# board_0_8v.net
KiCad netlist of a schematic drawn in EAGLE
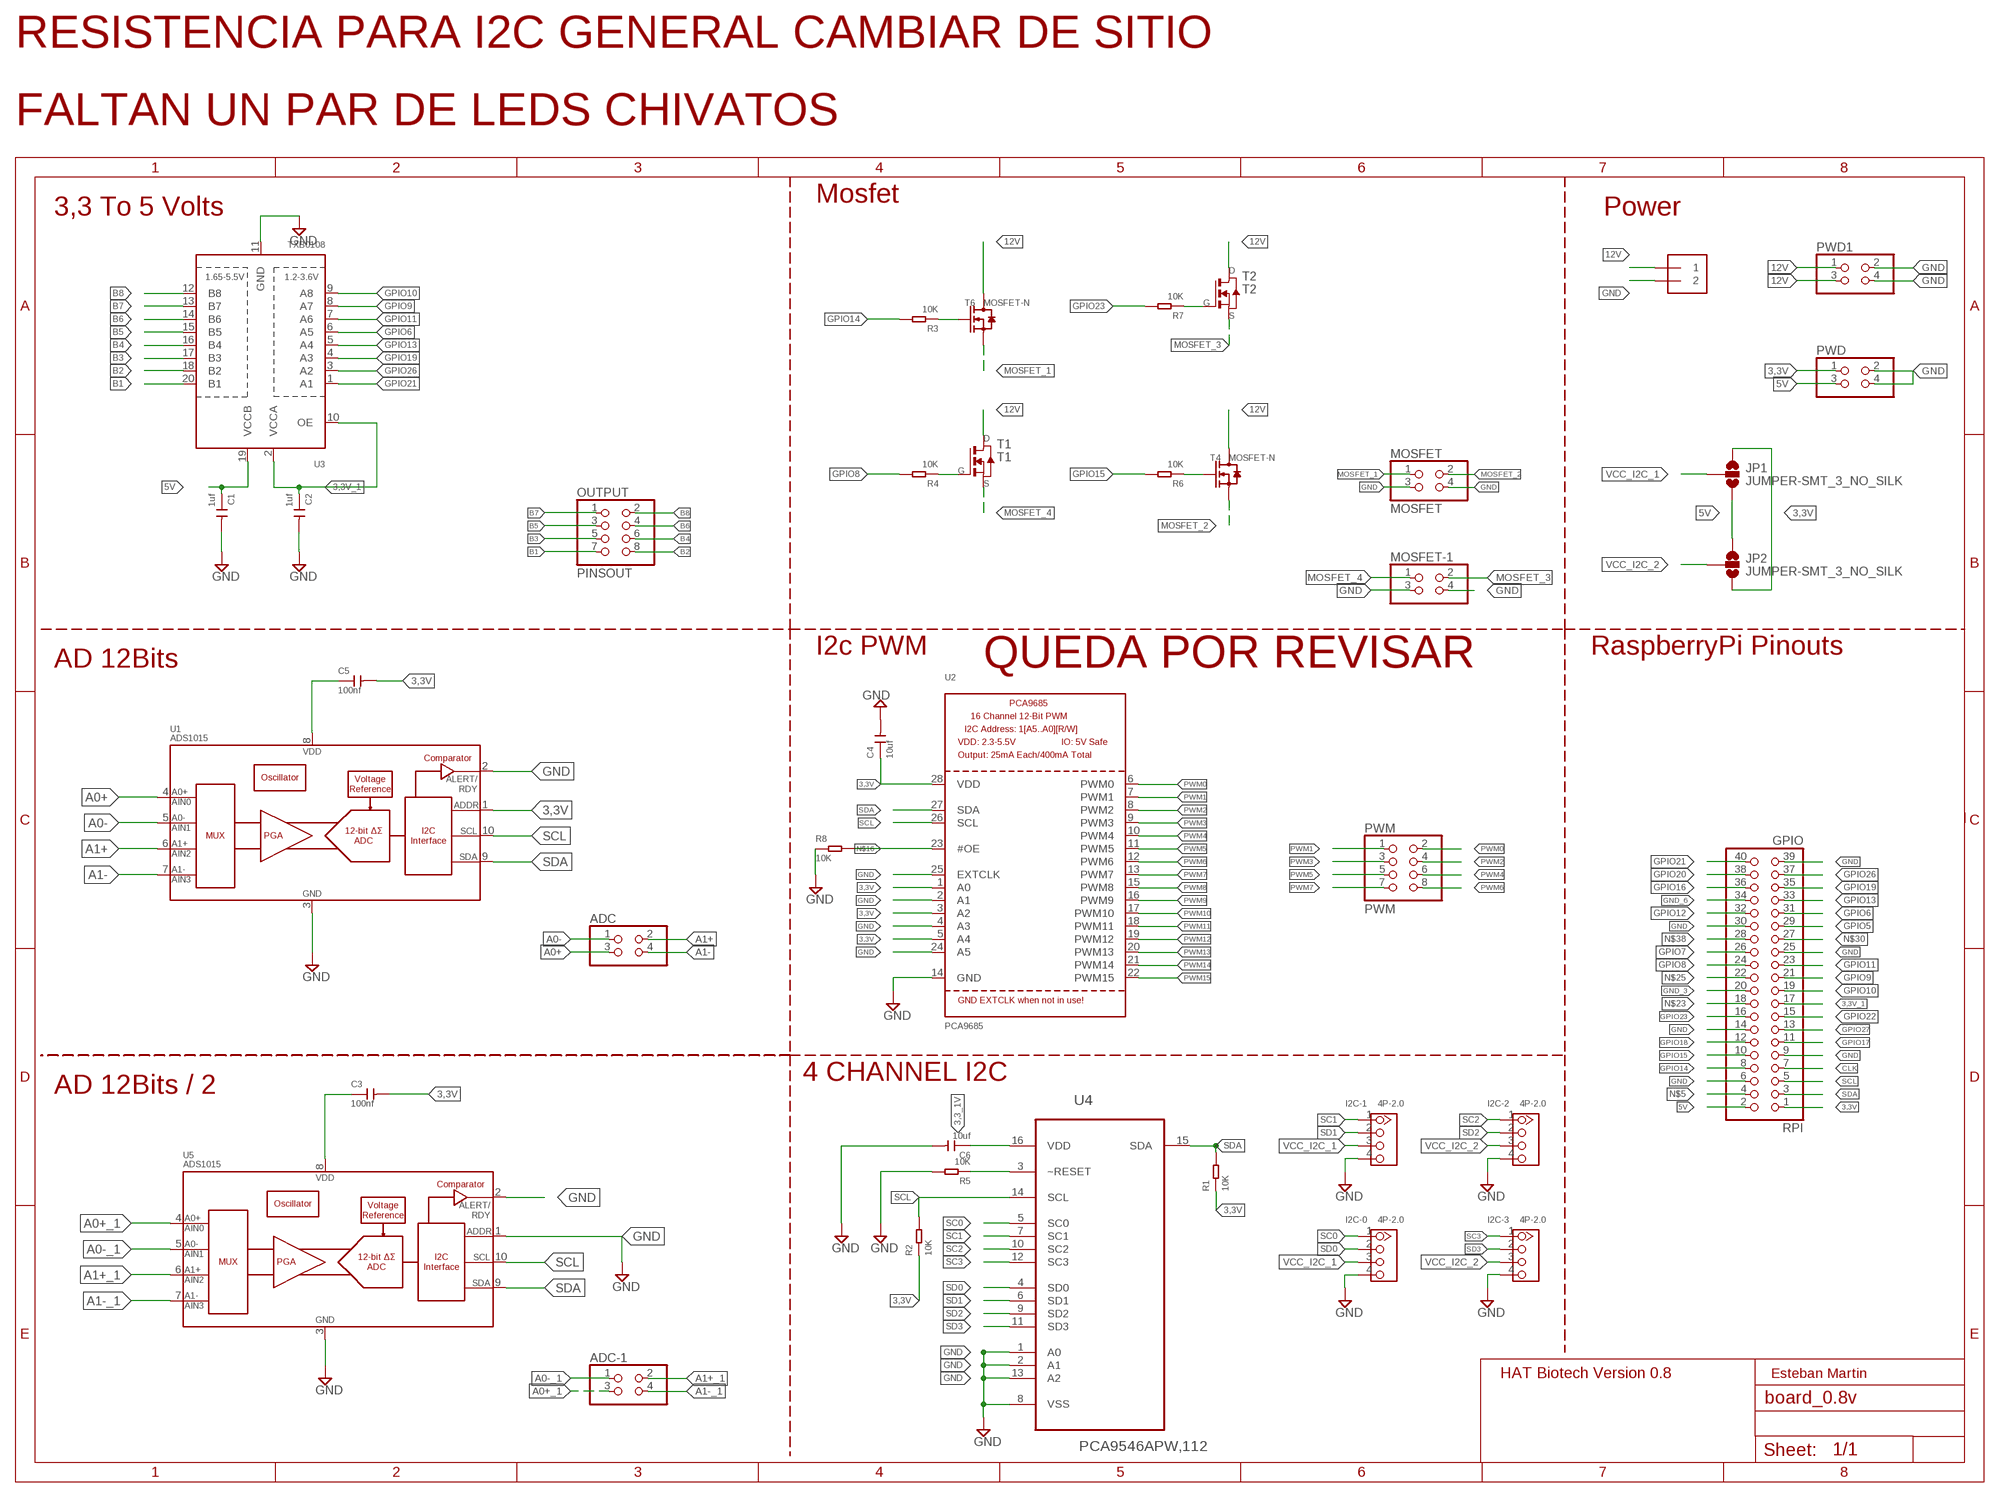
[diagram p0: schematic, sheet 1]

(export (version "E")
  (design (tool "Eeschema 10.0.6"))
  (components
    (comp (ref "ADC")
      (value "PINHD-2X2")
      (footprint "eagle-import:2X02")
      (libsource (lib "eagle-import") (part "PINHD-2X2"))
    )
    (comp (ref "ADC-1")
      (value "PINHD-2X2")
      (footprint "eagle-import:2X02")
      (libsource (lib "eagle-import") (part "PINHD-2X2"))
    )
    (comp (ref "C1")
      (value "1uf")
      (footprint "eagle-import:C0805")
      (fields (field (name "MPN") "CC0805KKX7R8BB105"))
      (libsource (lib "eagle-import") (part "CERAMIC-1UF-25V-10%-X7R(0805)"))
    )
    (comp (ref "C2")
      (value "1uf")
      (footprint "eagle-import:C0805")
      (fields (field (name "MPN") "CC0805KKX7R8BB105"))
      (libsource (lib "eagle-import") (part "CERAMIC-1UF-25V-10%-X7R(0805)"))
    )
    (comp (ref "C3")
      (value "100nf")
      (footprint "eagle-import:C0805")
      (fields (field (name "MPN") "CC0805KRX7R9BB104"))
      (libsource (lib "eagle-import") (part "CERAMIC-100NF-50V-10%-X7R(0805)"))
    )
    (comp (ref "C4")
      (value "10uf")
      (footprint "eagle-import:C0805")
      (fields (field (name "MPN") "CC0805KKX7R8BB105"))
      (libsource (lib "eagle-import") (part "CERAMIC-1UF-25V-10%-X7R(0805)"))
    )
    (comp (ref "C5")
      (value "100nf")
      (footprint "eagle-import:C0805")
      (fields (field (name "MPN") "CC0805KRX7R9BB104"))
      (libsource (lib "eagle-import") (part "CERAMIC-100NF-50V-10%-X7R(0805)"))
    )
    (comp (ref "C6")
      (value "10uf")
      (footprint "eagle-import:C0805")
      (fields (field (name "MPN") "CC0805KKX7R8BB105"))
      (libsource (lib "eagle-import") (part "CERAMIC-1UF-25V-10%-X7R(0805)"))
    )
    (comp (ref "I2C-0")
      (value "4P-2.0")
      (footprint "eagle-import:HW4-2.0")
      (libsource (lib "eagle-import") (part "GROVE-CONNECTOR-DIP(4P-2.0)"))
    )
    (comp (ref "I2C-1")
      (value "4P-2.0")
      (footprint "eagle-import:HW4-2.0")
      (libsource (lib "eagle-import") (part "GROVE-CONNECTOR-DIP(4P-2.0)"))
    )
    (comp (ref "I2C-2")
      (value "4P-2.0")
      (footprint "eagle-import:HW4-2.0")
      (libsource (lib "eagle-import") (part "GROVE-CONNECTOR-DIP(4P-2.0)"))
    )
    (comp (ref "I2C-3")
      (value "4P-2.0")
      (footprint "eagle-import:HW4-2.0")
      (libsource (lib "eagle-import") (part "GROVE-CONNECTOR-DIP(4P-2.0)"))
    )
    (comp (ref "INPUT")
      (value "1X2-3.5MM")
      (footprint "eagle-import:1X2-3.5MM")
      (libsource (lib "eagle-import") (part "1X2-3.5MM"))
    )
    (comp (ref "JP1")
      (value "JUMPER-SMT_3_NO_SILK")
      (footprint "eagle-import:SMT-JUMPER_3_NO_SILK")
      (libsource (lib "eagle-import") (part "JUMPER-SMT_3_NO_SILK"))
    )
    (comp (ref "JP2")
      (value "JUMPER-SMT_3_NO_SILK")
      (footprint "eagle-import:SMT-JUMPER_3_NO_SILK")
      (libsource (lib "eagle-import") (part "JUMPER-SMT_3_NO_SILK"))
    )
    (comp (ref "MOSFET")
      (value "MOSFET")
      (footprint "eagle-import:2X02")
      (libsource (lib "eagle-import") (part "PINHD-2X2"))
    )
    (comp (ref "MOSFET-1")
      (value "PINHD-2X2")
      (footprint "eagle-import:2X02")
      (libsource (lib "eagle-import") (part "PINHD-2X2"))
    )
    (comp (ref "OUTPUT")
      (value "PINSOUT")
      (footprint "eagle-import:2X04")
      (libsource (lib "eagle-import") (part "PINHD-2X4"))
    )
    (comp (ref "PWD")
      (value "PINHD-2X2")
      (footprint "eagle-import:2X02")
      (libsource (lib "eagle-import") (part "PINHD-2X2"))
    )
    (comp (ref "PWD1")
      (value "PINHD-2X2")
      (footprint "eagle-import:2X02")
      (libsource (lib "eagle-import") (part "PINHD-2X2"))
    )
    (comp (ref "PWM")
      (value "PWM")
      (footprint "eagle-import:2X04")
      (libsource (lib "eagle-import") (part "PINHD-2X4"))
    )
    (comp (ref "R1")
      (value "10K")
      (footprint "eagle-import:R0805")
      (fields (field (name "MPN") "RC0805FR-0710KL"))
      (libsource (lib "eagle-import") (part "SMD-RES-10K-1%-1/8W(0805)"))
    )
    (comp (ref "R2")
      (value "10K")
      (footprint "eagle-import:R0805")
      (fields (field (name "MPN") "RC0805FR-0710KL"))
      (libsource (lib "eagle-import") (part "SMD-RES-10K-1%-1/8W(0805)"))
    )
    (comp (ref "R3")
      (value "10K")
      (footprint "eagle-import:R0805")
      (fields (field (name "MPN") "RC0805FR-0710KL"))
      (libsource (lib "eagle-import") (part "SMD-RES-10K-1%-1/8W(0805)"))
    )
    (comp (ref "R4")
      (value "10K")
      (footprint "eagle-import:R0805")
      (fields (field (name "MPN") "RC0805FR-0710KL"))
      (libsource (lib "eagle-import") (part "SMD-RES-10K-1%-1/8W(0805)"))
    )
    (comp (ref "R5")
      (value "10K")
      (footprint "eagle-import:R0805")
      (fields (field (name "MPN") "RC0805FR-0710KL"))
      (libsource (lib "eagle-import") (part "SMD-RES-10K-1%-1/8W(0805)"))
    )
    (comp (ref "R6")
      (value "10K")
      (footprint "eagle-import:R0805")
      (fields (field (name "MPN") "RC0805FR-0710KL"))
      (libsource (lib "eagle-import") (part "SMD-RES-10K-1%-1/8W(0805)"))
    )
    (comp (ref "R7")
      (value "10K")
      (footprint "eagle-import:R0805")
      (fields (field (name "MPN") "RC0805FR-0710KL"))
      (libsource (lib "eagle-import") (part "SMD-RES-10K-1%-1/8W(0805)"))
    )
    (comp (ref "R8")
      (value "10K")
      (footprint "eagle-import:R0805")
      (fields (field (name "MPN") "RC0805FR-0710KL"))
      (libsource (lib "eagle-import") (part "SMD-RES-10K-1%-1/8W(0805)"))
    )
    (comp (ref "RPI")
      (value "GPIO")
      (footprint "eagle-import:2X20")
      (libsource (lib "eagle-import") (part "PINHD-2X20"))
    )
    (comp (ref "T1")
      (value "T1")
      (footprint "eagle-import:TO252")
      (libsource (lib "eagle-import") (part "NMOSFETTO252"))
    )
    (comp (ref "T2")
      (value "T2")
      (footprint "eagle-import:TO252")
      (libsource (lib "eagle-import") (part "NMOSFETTO252"))
    )
    (comp (ref "T4")
      (value "MOSFET-N")
      (footprint "eagle-import:SOT-23")
      (libsource (lib "eagle-import") (part "MOSFET-N"))
    )
    (comp (ref "T6")
      (value "MOSFET-N")
      (footprint "eagle-import:SOT-23")
      (libsource (lib "eagle-import") (part "MOSFET-N"))
    )
    (comp (ref "U1")
      (value "ADS1015")
      (footprint "eagle-import:MSOP10")
      (libsource (lib "eagle-import") (part "ADS1015"))
    )
    (comp (ref "U2")
      (value "PCA9685")
      (footprint "eagle-import:TSSOP28")
      (libsource (lib "eagle-import") (part "PCA9685"))
    )
    (comp (ref "U3")
      (value "TXB0108")
      (footprint "eagle-import:TSSOP20")
      (libsource (lib "eagle-import") (part "TXB0108PWR"))
    )
    (comp (ref "U4")
      (value "PCA9546APW,112")
      (footprint "eagle-import:SOP65P640X110-16N")
      (libsource (lib "eagle-import") (part "PCA9546APW,112"))
    )
    (comp (ref "U5")
      (value "ADS1015")
      (footprint "eagle-import:MSOP10")
      (libsource (lib "eagle-import") (part "ADS1015"))
    )
  )
  (nets
    (net (code "1") (name "3,3V") (class "Default")
      (node (ref "C3") (pin "2") (pinfunction "2_2") (pintype "passive"))
      (node (ref "C4") (pin "1") (pinfunction "1_1") (pintype "passive"))
      (node (ref "C5") (pin "2") (pinfunction "2_2") (pintype "passive"))
      (node (ref "JP1") (pin "1") (pinfunction "1_1") (pintype "passive"))
      (node (ref "JP2") (pin "3") (pinfunction "3_3") (pintype "passive"))
      (node (ref "PWD") (pin "1") (pinfunction "1_1") (pintype "passive"))
      (node (ref "R1") (pin "1") (pinfunction "1_1") (pintype "passive"))
      (node (ref "R2") (pin "1") (pinfunction "1_1") (pintype "passive"))
      (node (ref "RPI") (pin "1") (pinfunction "1_1") (pintype "passive"))
      (node (ref "U1") (pin "1") (pinfunction "ADDR_1") (pintype "bidirectional"))
      (node (ref "U2") (pin "1") (pinfunction "A0_1") (pintype "bidirectional"))
      (node (ref "U2") (pin "28") (pinfunction "VDD_28") (pintype "power_in"))
      (node (ref "U2") (pin "3") (pinfunction "A2_3") (pintype "bidirectional"))
      (node (ref "U2") (pin "5") (pinfunction "A4_5") (pintype "bidirectional"))
    )
    (net (code "2") (name "3,3V_1") (class "Default")
      (node (ref "C2") (pin "1") (pinfunction "1_1") (pintype "passive"))
      (node (ref "RPI") (pin "17") (pinfunction "17_17") (pintype "passive"))
      (node (ref "U3") (pin "10") (pinfunction "OE_10") (pintype "bidirectional"))
      (node (ref "U3") (pin "2") (pinfunction "VCCA_2") (pintype "bidirectional"))
    )
    (net (code "3") (name "3,3_1V") (class "Default")
      (node (ref "C6") (pin "1") (pinfunction "1_1") (pintype "passive"))
      (node (ref "U4") (pin "16") (pinfunction "VDD_16") (pintype "power_in"))
    )
    (net (code "4") (name "5V") (class "Default")
      (node (ref "C1") (pin "1") (pinfunction "1_1") (pintype "passive"))
      (node (ref "JP1") (pin "3") (pinfunction "3_3") (pintype "passive"))
      (node (ref "JP2") (pin "1") (pinfunction "1_1") (pintype "passive"))
      (node (ref "PWD") (pin "3") (pinfunction "3_3") (pintype "passive"))
      (node (ref "RPI") (pin "2") (pinfunction "2_2") (pintype "passive"))
      (node (ref "U3") (pin "19") (pinfunction "VCCB_19") (pintype "bidirectional"))
    )
    (net (code "5") (name "12V") (class "Default")
      (node (ref "INPUT") (pin "1") (pinfunction "1_1") (pintype "passive"))
      (node (ref "PWD1") (pin "1") (pinfunction "1_1") (pintype "passive"))
      (node (ref "PWD1") (pin "3") (pinfunction "3_3") (pintype "passive"))
      (node (ref "T1") (pin "3") (pinfunction "D_3") (pintype "passive"))
      (node (ref "T2") (pin "3") (pinfunction "D_3") (pintype "passive"))
      (node (ref "T4") (pin "3") (pinfunction "D_3") (pintype "passive"))
      (node (ref "T6") (pin "3") (pinfunction "D_3") (pintype "passive"))
    )
    (net (code "6") (name "A0+") (class "Default")
      (node (ref "ADC") (pin "3") (pinfunction "3_3") (pintype "passive"))
      (node (ref "U1") (pin "4") (pinfunction "AIN0_4") (pintype "bidirectional"))
    )
    (net (code "7") (name "A0+_1") (class "Default")
      (node (ref "ADC-1") (pin "3") (pinfunction "3_3") (pintype "passive"))
      (node (ref "U5") (pin "4") (pinfunction "AIN0_4") (pintype "bidirectional"))
    )
    (net (code "8") (name "A0-") (class "Default")
      (node (ref "ADC") (pin "1") (pinfunction "1_1") (pintype "passive"))
      (node (ref "U1") (pin "5") (pinfunction "AIN1_5") (pintype "bidirectional"))
    )
    (net (code "9") (name "A0-_1") (class "Default")
      (node (ref "ADC-1") (pin "1") (pinfunction "1_1") (pintype "passive"))
      (node (ref "U5") (pin "5") (pinfunction "AIN1_5") (pintype "bidirectional"))
    )
    (net (code "10") (name "A1+") (class "Default")
      (node (ref "ADC") (pin "2") (pinfunction "2_2") (pintype "passive"))
      (node (ref "U1") (pin "6") (pinfunction "AIN2_6") (pintype "bidirectional"))
    )
    (net (code "11") (name "A1+_1") (class "Default")
      (node (ref "ADC-1") (pin "2") (pinfunction "2_2") (pintype "passive"))
      (node (ref "U5") (pin "6") (pinfunction "AIN2_6") (pintype "bidirectional"))
    )
    (net (code "12") (name "A1-") (class "Default")
      (node (ref "ADC") (pin "4") (pinfunction "4_4") (pintype "passive"))
      (node (ref "U1") (pin "7") (pinfunction "AIN3_7") (pintype "bidirectional"))
    )
    (net (code "13") (name "A1-_1") (class "Default")
      (node (ref "ADC-1") (pin "4") (pinfunction "4_4") (pintype "passive"))
      (node (ref "U5") (pin "7") (pinfunction "AIN3_7") (pintype "bidirectional"))
    )
    (net (code "14") (name "B1") (class "Default")
      (node (ref "OUTPUT") (pin "7") (pinfunction "7_7") (pintype "passive"))
      (node (ref "U3") (pin "20") (pinfunction "B1_20") (pintype "bidirectional"))
    )
    (net (code "15") (name "B2") (class "Default")
      (node (ref "OUTPUT") (pin "8") (pinfunction "8_8") (pintype "passive"))
      (node (ref "U3") (pin "18") (pinfunction "B2_18") (pintype "bidirectional"))
    )
    (net (code "16") (name "B3") (class "Default")
      (node (ref "OUTPUT") (pin "5") (pinfunction "5_5") (pintype "passive"))
      (node (ref "U3") (pin "17") (pinfunction "B3_17") (pintype "bidirectional"))
    )
    (net (code "17") (name "B4") (class "Default")
      (node (ref "OUTPUT") (pin "6") (pinfunction "6_6") (pintype "passive"))
      (node (ref "U3") (pin "16") (pinfunction "B4_16") (pintype "bidirectional"))
    )
    (net (code "18") (name "B5") (class "Default")
      (node (ref "OUTPUT") (pin "3") (pinfunction "3_3") (pintype "passive"))
      (node (ref "U3") (pin "15") (pinfunction "B5_15") (pintype "bidirectional"))
    )
    (net (code "19") (name "B6") (class "Default")
      (node (ref "OUTPUT") (pin "4") (pinfunction "4_4") (pintype "passive"))
      (node (ref "U3") (pin "14") (pinfunction "B6_14") (pintype "bidirectional"))
    )
    (net (code "20") (name "B7") (class "Default")
      (node (ref "OUTPUT") (pin "1") (pinfunction "1_1") (pintype "passive"))
      (node (ref "U3") (pin "13") (pinfunction "B7_13") (pintype "bidirectional"))
    )
    (net (code "21") (name "B8") (class "Default")
      (node (ref "OUTPUT") (pin "2") (pinfunction "2_2") (pintype "passive"))
      (node (ref "U3") (pin "12") (pinfunction "B8_12") (pintype "bidirectional"))
    )
    (net (code "22") (name "CLK") (class "Default")
      (node (ref "RPI") (pin "7") (pinfunction "7_7") (pintype "passive"))
    )
    (net (code "23") (name "GND") (class "Default")
      (node (ref "C1") (pin "2") (pinfunction "2_2") (pintype "passive"))
      (node (ref "C2") (pin "2") (pinfunction "2_2") (pintype "passive"))
      (node (ref "C4") (pin "2") (pinfunction "2_2") (pintype "passive"))
      (node (ref "C6") (pin "2") (pinfunction "2_2") (pintype "passive"))
      (node (ref "I2C-0") (pin "4") (pinfunction "4_4") (pintype "bidirectional"))
      (node (ref "I2C-1") (pin "4") (pinfunction "4_4") (pintype "bidirectional"))
      (node (ref "I2C-2") (pin "4") (pinfunction "4_4") (pintype "bidirectional"))
      (node (ref "I2C-3") (pin "4") (pinfunction "4_4") (pintype "bidirectional"))
      (node (ref "INPUT") (pin "2") (pinfunction "2_2") (pintype "passive"))
      (node (ref "MOSFET") (pin "3") (pinfunction "3_3") (pintype "passive"))
      (node (ref "MOSFET") (pin "4") (pinfunction "4_4") (pintype "passive"))
      (node (ref "MOSFET-1") (pin "3") (pinfunction "3_3") (pintype "passive"))
      (node (ref "MOSFET-1") (pin "4") (pinfunction "4_4") (pintype "passive"))
      (node (ref "PWD") (pin "2") (pinfunction "2_2") (pintype "passive"))
      (node (ref "PWD") (pin "4") (pinfunction "4_4") (pintype "passive"))
      (node (ref "PWD1") (pin "2") (pinfunction "2_2") (pintype "passive"))
      (node (ref "PWD1") (pin "4") (pinfunction "4_4") (pintype "passive"))
      (node (ref "R5") (pin "2") (pinfunction "2_2") (pintype "passive"))
      (node (ref "R8") (pin "1") (pinfunction "1_1") (pintype "passive"))
      (node (ref "RPI") (pin "14") (pinfunction "14_14") (pintype "passive"))
      (node (ref "RPI") (pin "25") (pinfunction "25_25") (pintype "passive"))
      (node (ref "RPI") (pin "30") (pinfunction "30_30") (pintype "passive"))
      (node (ref "RPI") (pin "39") (pinfunction "39_39") (pintype "passive"))
      (node (ref "RPI") (pin "6") (pinfunction "6_6") (pintype "passive"))
      (node (ref "RPI") (pin "9") (pinfunction "9_9") (pintype "passive"))
      (node (ref "U1") (pin "2") (pinfunction "ALERT/RDY_2") (pintype "bidirectional"))
      (node (ref "U1") (pin "3") (pinfunction "VSS_3") (pintype "bidirectional"))
      (node (ref "U2") (pin "14") (pinfunction "GND_14") (pintype "power_in"))
      (node (ref "U2") (pin "2") (pinfunction "A1_2") (pintype "bidirectional"))
      (node (ref "U2") (pin "24") (pinfunction "A5_24") (pintype "bidirectional"))
      (node (ref "U2") (pin "25") (pinfunction "EXTCLK_25") (pintype "input"))
      (node (ref "U2") (pin "4") (pinfunction "A3_4") (pintype "bidirectional"))
      (node (ref "U3") (pin "11") (pinfunction "GND_11") (pintype "bidirectional"))
      (node (ref "U4") (pin "1") (pinfunction "A0_1") (pintype "input"))
      (node (ref "U4") (pin "13") (pinfunction "A2_13") (pintype "input"))
      (node (ref "U4") (pin "2") (pinfunction "A1_2") (pintype "input"))
      (node (ref "U4") (pin "8") (pinfunction "VSS_8") (pintype "passive"))
      (node (ref "U5") (pin "1") (pinfunction "ADDR_1") (pintype "bidirectional"))
      (node (ref "U5") (pin "2") (pinfunction "ALERT/RDY_2") (pintype "bidirectional"))
      (node (ref "U5") (pin "3") (pinfunction "VSS_3") (pintype "bidirectional"))
    )
    (net (code "24") (name "GND_3") (class "Default")
      (node (ref "RPI") (pin "20") (pinfunction "20_20") (pintype "passive"))
    )
    (net (code "25") (name "GND_6") (class "Default")
      (node (ref "RPI") (pin "34") (pinfunction "34_34") (pintype "passive"))
    )
    (net (code "26") (name "GPIO5") (class "Default")
      (node (ref "RPI") (pin "29") (pinfunction "29_29") (pintype "passive"))
    )
    (net (code "27") (name "GPIO6") (class "Default")
      (node (ref "RPI") (pin "31") (pinfunction "31_31") (pintype "passive"))
      (node (ref "U3") (pin "6") (pinfunction "A5_6") (pintype "bidirectional"))
    )
    (net (code "28") (name "GPIO7") (class "Default")
      (node (ref "RPI") (pin "26") (pinfunction "26_26") (pintype "passive"))
    )
    (net (code "29") (name "GPIO8") (class "Default")
      (node (ref "R4") (pin "2") (pinfunction "2_2") (pintype "passive"))
      (node (ref "RPI") (pin "24") (pinfunction "24_24") (pintype "passive"))
    )
    (net (code "30") (name "GPIO9") (class "Default")
      (node (ref "RPI") (pin "21") (pinfunction "21_21") (pintype "passive"))
      (node (ref "U3") (pin "8") (pinfunction "A7_8") (pintype "bidirectional"))
    )
    (net (code "31") (name "GPIO10") (class "Default")
      (node (ref "RPI") (pin "19") (pinfunction "19_19") (pintype "passive"))
      (node (ref "U3") (pin "9") (pinfunction "A8_9") (pintype "bidirectional"))
    )
    (net (code "32") (name "GPIO11") (class "Default")
      (node (ref "RPI") (pin "23") (pinfunction "23_23") (pintype "passive"))
      (node (ref "U3") (pin "7") (pinfunction "A6_7") (pintype "bidirectional"))
    )
    (net (code "33") (name "GPIO12") (class "Default")
      (node (ref "RPI") (pin "32") (pinfunction "32_32") (pintype "passive"))
    )
    (net (code "34") (name "GPIO13") (class "Default")
      (node (ref "RPI") (pin "33") (pinfunction "33_33") (pintype "passive"))
      (node (ref "U3") (pin "5") (pinfunction "A4_5") (pintype "bidirectional"))
    )
    (net (code "35") (name "GPIO14") (class "Default")
      (node (ref "R3") (pin "2") (pinfunction "2_2") (pintype "passive"))
      (node (ref "RPI") (pin "8") (pinfunction "8_8") (pintype "passive"))
    )
    (net (code "36") (name "GPIO15") (class "Default")
      (node (ref "R6") (pin "2") (pinfunction "2_2") (pintype "passive"))
      (node (ref "RPI") (pin "10") (pinfunction "10_10") (pintype "passive"))
    )
    (net (code "37") (name "GPIO16") (class "Default")
      (node (ref "RPI") (pin "36") (pinfunction "36_36") (pintype "passive"))
    )
    (net (code "38") (name "GPIO17") (class "Default")
      (node (ref "RPI") (pin "11") (pinfunction "11_11") (pintype "passive"))
    )
    (net (code "39") (name "GPIO18") (class "Default")
      (node (ref "RPI") (pin "12") (pinfunction "12_12") (pintype "passive"))
    )
    (net (code "40") (name "GPIO19") (class "Default")
      (node (ref "RPI") (pin "35") (pinfunction "35_35") (pintype "passive"))
      (node (ref "U3") (pin "4") (pinfunction "A3_4") (pintype "bidirectional"))
    )
    (net (code "41") (name "GPIO20") (class "Default")
      (node (ref "RPI") (pin "38") (pinfunction "38_38") (pintype "passive"))
    )
    (net (code "42") (name "GPIO21") (class "Default")
      (node (ref "RPI") (pin "40") (pinfunction "40_40") (pintype "passive"))
      (node (ref "U3") (pin "1") (pinfunction "A1_1") (pintype "bidirectional"))
    )
    (net (code "43") (name "GPIO22") (class "Default")
      (node (ref "RPI") (pin "15") (pinfunction "15_15") (pintype "passive"))
    )
    (net (code "44") (name "GPIO23") (class "Default")
      (node (ref "R7") (pin "2") (pinfunction "2_2") (pintype "passive"))
      (node (ref "RPI") (pin "16") (pinfunction "16_16") (pintype "passive"))
    )
    (net (code "45") (name "GPIO26") (class "Default")
      (node (ref "RPI") (pin "37") (pinfunction "37_37") (pintype "passive"))
      (node (ref "U3") (pin "3") (pinfunction "A2_3") (pintype "bidirectional"))
    )
    (net (code "46") (name "GPIO27") (class "Default")
      (node (ref "RPI") (pin "13") (pinfunction "13_13") (pintype "passive"))
    )
    (net (code "47") (name "MOSFET_1") (class "Default")
      (node (ref "MOSFET") (pin "1") (pinfunction "1_1") (pintype "passive"))
      (node (ref "T6") (pin "2") (pinfunction "S_2") (pintype "passive"))
    )
    (net (code "48") (name "MOSFET_2") (class "Default")
      (node (ref "MOSFET") (pin "2") (pinfunction "2_2") (pintype "passive"))
      (node (ref "T4") (pin "2") (pinfunction "S_2") (pintype "passive"))
    )
    (net (code "49") (name "MOSFET_3") (class "Default")
      (node (ref "MOSFET-1") (pin "2") (pinfunction "2_2") (pintype "passive"))
      (node (ref "T2") (pin "2") (pinfunction "S_2") (pintype "passive"))
    )
    (net (code "50") (name "MOSFET_4") (class "Default")
      (node (ref "MOSFET-1") (pin "1") (pinfunction "1_1") (pintype "passive"))
      (node (ref "T1") (pin "2") (pinfunction "S_2") (pintype "passive"))
    )
    (net (code "51") (name "N$5") (class "Default")
      (node (ref "RPI") (pin "4") (pinfunction "4_4") (pintype "passive"))
    )
    (net (code "52") (name "N$16") (class "Default")
      (node (ref "R8") (pin "2") (pinfunction "2_2") (pintype "passive"))
      (node (ref "U2") (pin "23") (pinfunction "#OE_23") (pintype "input"))
    )
    (net (code "53") (name "N$23") (class "Default")
      (node (ref "RPI") (pin "18") (pinfunction "18_18") (pintype "passive"))
    )
    (net (code "54") (name "N$25") (class "Default")
      (node (ref "RPI") (pin "22") (pinfunction "22_22") (pintype "passive"))
    )
    (net (code "55") (name "N$30") (class "Default")
      (node (ref "RPI") (pin "27") (pinfunction "27_27") (pintype "passive"))
    )
    (net (code "56") (name "N$38") (class "Default")
      (node (ref "RPI") (pin "28") (pinfunction "28_28") (pintype "passive"))
    )
    (net (code "57") (name "Net-(T1-G)") (class "Default")
      (node (ref "R4") (pin "1") (pinfunction "1_1") (pintype "passive"))
      (node (ref "T1") (pin "1") (pinfunction "G_1") (pintype "passive"))
    )
    (net (code "58") (name "Net-(T2-G)") (class "Default")
      (node (ref "R7") (pin "1") (pinfunction "1_1") (pintype "passive"))
      (node (ref "T2") (pin "1") (pinfunction "G_1") (pintype "passive"))
    )
    (net (code "59") (name "Net-(T4-G)") (class "Default")
      (node (ref "R6") (pin "1") (pinfunction "1_1") (pintype "passive"))
      (node (ref "T4") (pin "1") (pinfunction "G_1") (pintype "passive"))
    )
    (net (code "60") (name "Net-(T6-G)") (class "Default")
      (node (ref "R3") (pin "1") (pinfunction "1_1") (pintype "passive"))
      (node (ref "T6") (pin "1") (pinfunction "G_1") (pintype "passive"))
    )
    (net (code "61") (name "Net-(U1-VDD)") (class "Default")
      (node (ref "C5") (pin "1") (pinfunction "1_1") (pintype "passive"))
      (node (ref "U1") (pin "8") (pinfunction "VDD_8") (pintype "bidirectional"))
    )
    (net (code "62") (name "Net-(U4-~{RESET})") (class "Default")
      (node (ref "R5") (pin "1") (pinfunction "1_1") (pintype "passive"))
      (node (ref "U4") (pin "3") (pinfunction "~{RESET}_3") (pintype "input"))
    )
    (net (code "63") (name "Net-(U5-VDD)") (class "Default")
      (node (ref "C3") (pin "1") (pinfunction "1_1") (pintype "passive"))
      (node (ref "U5") (pin "8") (pinfunction "VDD_8") (pintype "bidirectional"))
    )
    (net (code "64") (name "PWM0") (class "Default")
      (node (ref "PWM") (pin "2") (pinfunction "2_2") (pintype "passive"))
      (node (ref "U2") (pin "6") (pinfunction "PWM0_6") (pintype "output"))
    )
    (net (code "65") (name "PWM1") (class "Default")
      (node (ref "PWM") (pin "1") (pinfunction "1_1") (pintype "passive"))
      (node (ref "U2") (pin "7") (pinfunction "PWM1_7") (pintype "output"))
    )
    (net (code "66") (name "PWM2") (class "Default")
      (node (ref "PWM") (pin "4") (pinfunction "4_4") (pintype "passive"))
      (node (ref "U2") (pin "8") (pinfunction "PWM2_8") (pintype "output"))
    )
    (net (code "67") (name "PWM3") (class "Default")
      (node (ref "PWM") (pin "3") (pinfunction "3_3") (pintype "passive"))
      (node (ref "U2") (pin "9") (pinfunction "PWM3_9") (pintype "output"))
    )
    (net (code "68") (name "PWM4") (class "Default")
      (node (ref "PWM") (pin "6") (pinfunction "6_6") (pintype "passive"))
      (node (ref "U2") (pin "10") (pinfunction "PWM4_10") (pintype "output"))
    )
    (net (code "69") (name "PWM5") (class "Default")
      (node (ref "PWM") (pin "5") (pinfunction "5_5") (pintype "passive"))
      (node (ref "U2") (pin "11") (pinfunction "PWM5_11") (pintype "output"))
    )
    (net (code "70") (name "PWM6") (class "Default")
      (node (ref "PWM") (pin "8") (pinfunction "8_8") (pintype "passive"))
      (node (ref "U2") (pin "12") (pinfunction "PWM6_12") (pintype "output"))
    )
    (net (code "71") (name "PWM7") (class "Default")
      (node (ref "PWM") (pin "7") (pinfunction "7_7") (pintype "passive"))
      (node (ref "U2") (pin "13") (pinfunction "PWM7_13") (pintype "output"))
    )
    (net (code "72") (name "PWM8") (class "Default")
      (node (ref "U2") (pin "15") (pinfunction "PWM8_15") (pintype "output"))
    )
    (net (code "73") (name "PWM9") (class "Default")
      (node (ref "U2") (pin "16") (pinfunction "PWM9_16") (pintype "output"))
    )
    (net (code "74") (name "PWM10") (class "Default")
      (node (ref "U2") (pin "17") (pinfunction "PWM10_17") (pintype "output"))
    )
    (net (code "75") (name "PWM11") (class "Default")
      (node (ref "U2") (pin "18") (pinfunction "PWM11_18") (pintype "output"))
    )
    (net (code "76") (name "PWM12") (class "Default")
      (node (ref "U2") (pin "19") (pinfunction "PWM12_19") (pintype "output"))
    )
    (net (code "77") (name "PWM13") (class "Default")
      (node (ref "U2") (pin "20") (pinfunction "PWM13_20") (pintype "output"))
    )
    (net (code "78") (name "PWM14") (class "Default")
      (node (ref "U2") (pin "21") (pinfunction "PWM14_21") (pintype "output"))
    )
    (net (code "79") (name "PWM15") (class "Default")
      (node (ref "U2") (pin "22") (pinfunction "PWM15_22") (pintype "output"))
    )
    (net (code "80") (name "SC0") (class "Default")
      (node (ref "I2C-0") (pin "1") (pinfunction "1_1") (pintype "bidirectional"))
      (node (ref "U4") (pin "5") (pinfunction "SC0_5") (pintype "input"))
    )
    (net (code "81") (name "SC1") (class "Default")
      (node (ref "I2C-1") (pin "1") (pinfunction "1_1") (pintype "bidirectional"))
      (node (ref "U4") (pin "7") (pinfunction "SC1_7") (pintype "input"))
    )
    (net (code "82") (name "SC2") (class "Default")
      (node (ref "I2C-2") (pin "1") (pinfunction "1_1") (pintype "bidirectional"))
      (node (ref "U4") (pin "10") (pinfunction "SC2_10") (pintype "input"))
    )
    (net (code "83") (name "SC3") (class "Default")
      (node (ref "I2C-3") (pin "1") (pinfunction "1_1") (pintype "bidirectional"))
      (node (ref "U4") (pin "12") (pinfunction "SC3_12") (pintype "input"))
    )
    (net (code "84") (name "SCL") (class "Default")
      (node (ref "R2") (pin "2") (pinfunction "2_2") (pintype "passive"))
      (node (ref "RPI") (pin "5") (pinfunction "5_5") (pintype "passive"))
      (node (ref "U1") (pin "10") (pinfunction "SCL_10") (pintype "bidirectional"))
      (node (ref "U2") (pin "26") (pinfunction "SCL_26") (pintype "bidirectional"))
      (node (ref "U4") (pin "14") (pinfunction "SCL_14") (pintype "bidirectional"))
      (node (ref "U5") (pin "10") (pinfunction "SCL_10") (pintype "bidirectional"))
    )
    (net (code "85") (name "SD0") (class "Default")
      (node (ref "I2C-0") (pin "2") (pinfunction "2_2") (pintype "bidirectional"))
      (node (ref "U4") (pin "4") (pinfunction "SD0_4") (pintype "input"))
    )
    (net (code "86") (name "SD1") (class "Default")
      (node (ref "I2C-1") (pin "2") (pinfunction "2_2") (pintype "bidirectional"))
      (node (ref "U4") (pin "6") (pinfunction "SD1_6") (pintype "input"))
    )
    (net (code "87") (name "SD2") (class "Default")
      (node (ref "I2C-2") (pin "2") (pinfunction "2_2") (pintype "bidirectional"))
      (node (ref "U4") (pin "9") (pinfunction "SD2_9") (pintype "input"))
    )
    (net (code "88") (name "SD3") (class "Default")
      (node (ref "I2C-3") (pin "2") (pinfunction "2_2") (pintype "bidirectional"))
      (node (ref "U4") (pin "11") (pinfunction "SD3_11") (pintype "input"))
    )
    (net (code "89") (name "SDA") (class "Default")
      (node (ref "R1") (pin "2") (pinfunction "2_2") (pintype "passive"))
      (node (ref "RPI") (pin "3") (pinfunction "3_3") (pintype "passive"))
      (node (ref "U1") (pin "9") (pinfunction "SDA_9") (pintype "bidirectional"))
      (node (ref "U2") (pin "27") (pinfunction "SDA_27") (pintype "bidirectional"))
      (node (ref "U4") (pin "15") (pinfunction "SDA_15") (pintype "bidirectional"))
      (node (ref "U5") (pin "9") (pinfunction "SDA_9") (pintype "bidirectional"))
    )
    (net (code "90") (name "VCC_I2C_1") (class "Default")
      (node (ref "I2C-0") (pin "3") (pinfunction "3_3") (pintype "bidirectional"))
      (node (ref "I2C-1") (pin "3") (pinfunction "3_3") (pintype "bidirectional"))
      (node (ref "JP1") (pin "2") (pinfunction "2_2") (pintype "passive"))
    )
    (net (code "91") (name "VCC_I2C_2") (class "Default")
      (node (ref "I2C-2") (pin "3") (pinfunction "3_3") (pintype "bidirectional"))
      (node (ref "I2C-3") (pin "3") (pinfunction "3_3") (pintype "bidirectional"))
      (node (ref "JP2") (pin "2") (pinfunction "2_2") (pintype "passive"))
    )
  )
)
